# P26_EXPORT.net
KiCad netlist of a schematic drawn in Altium Designer
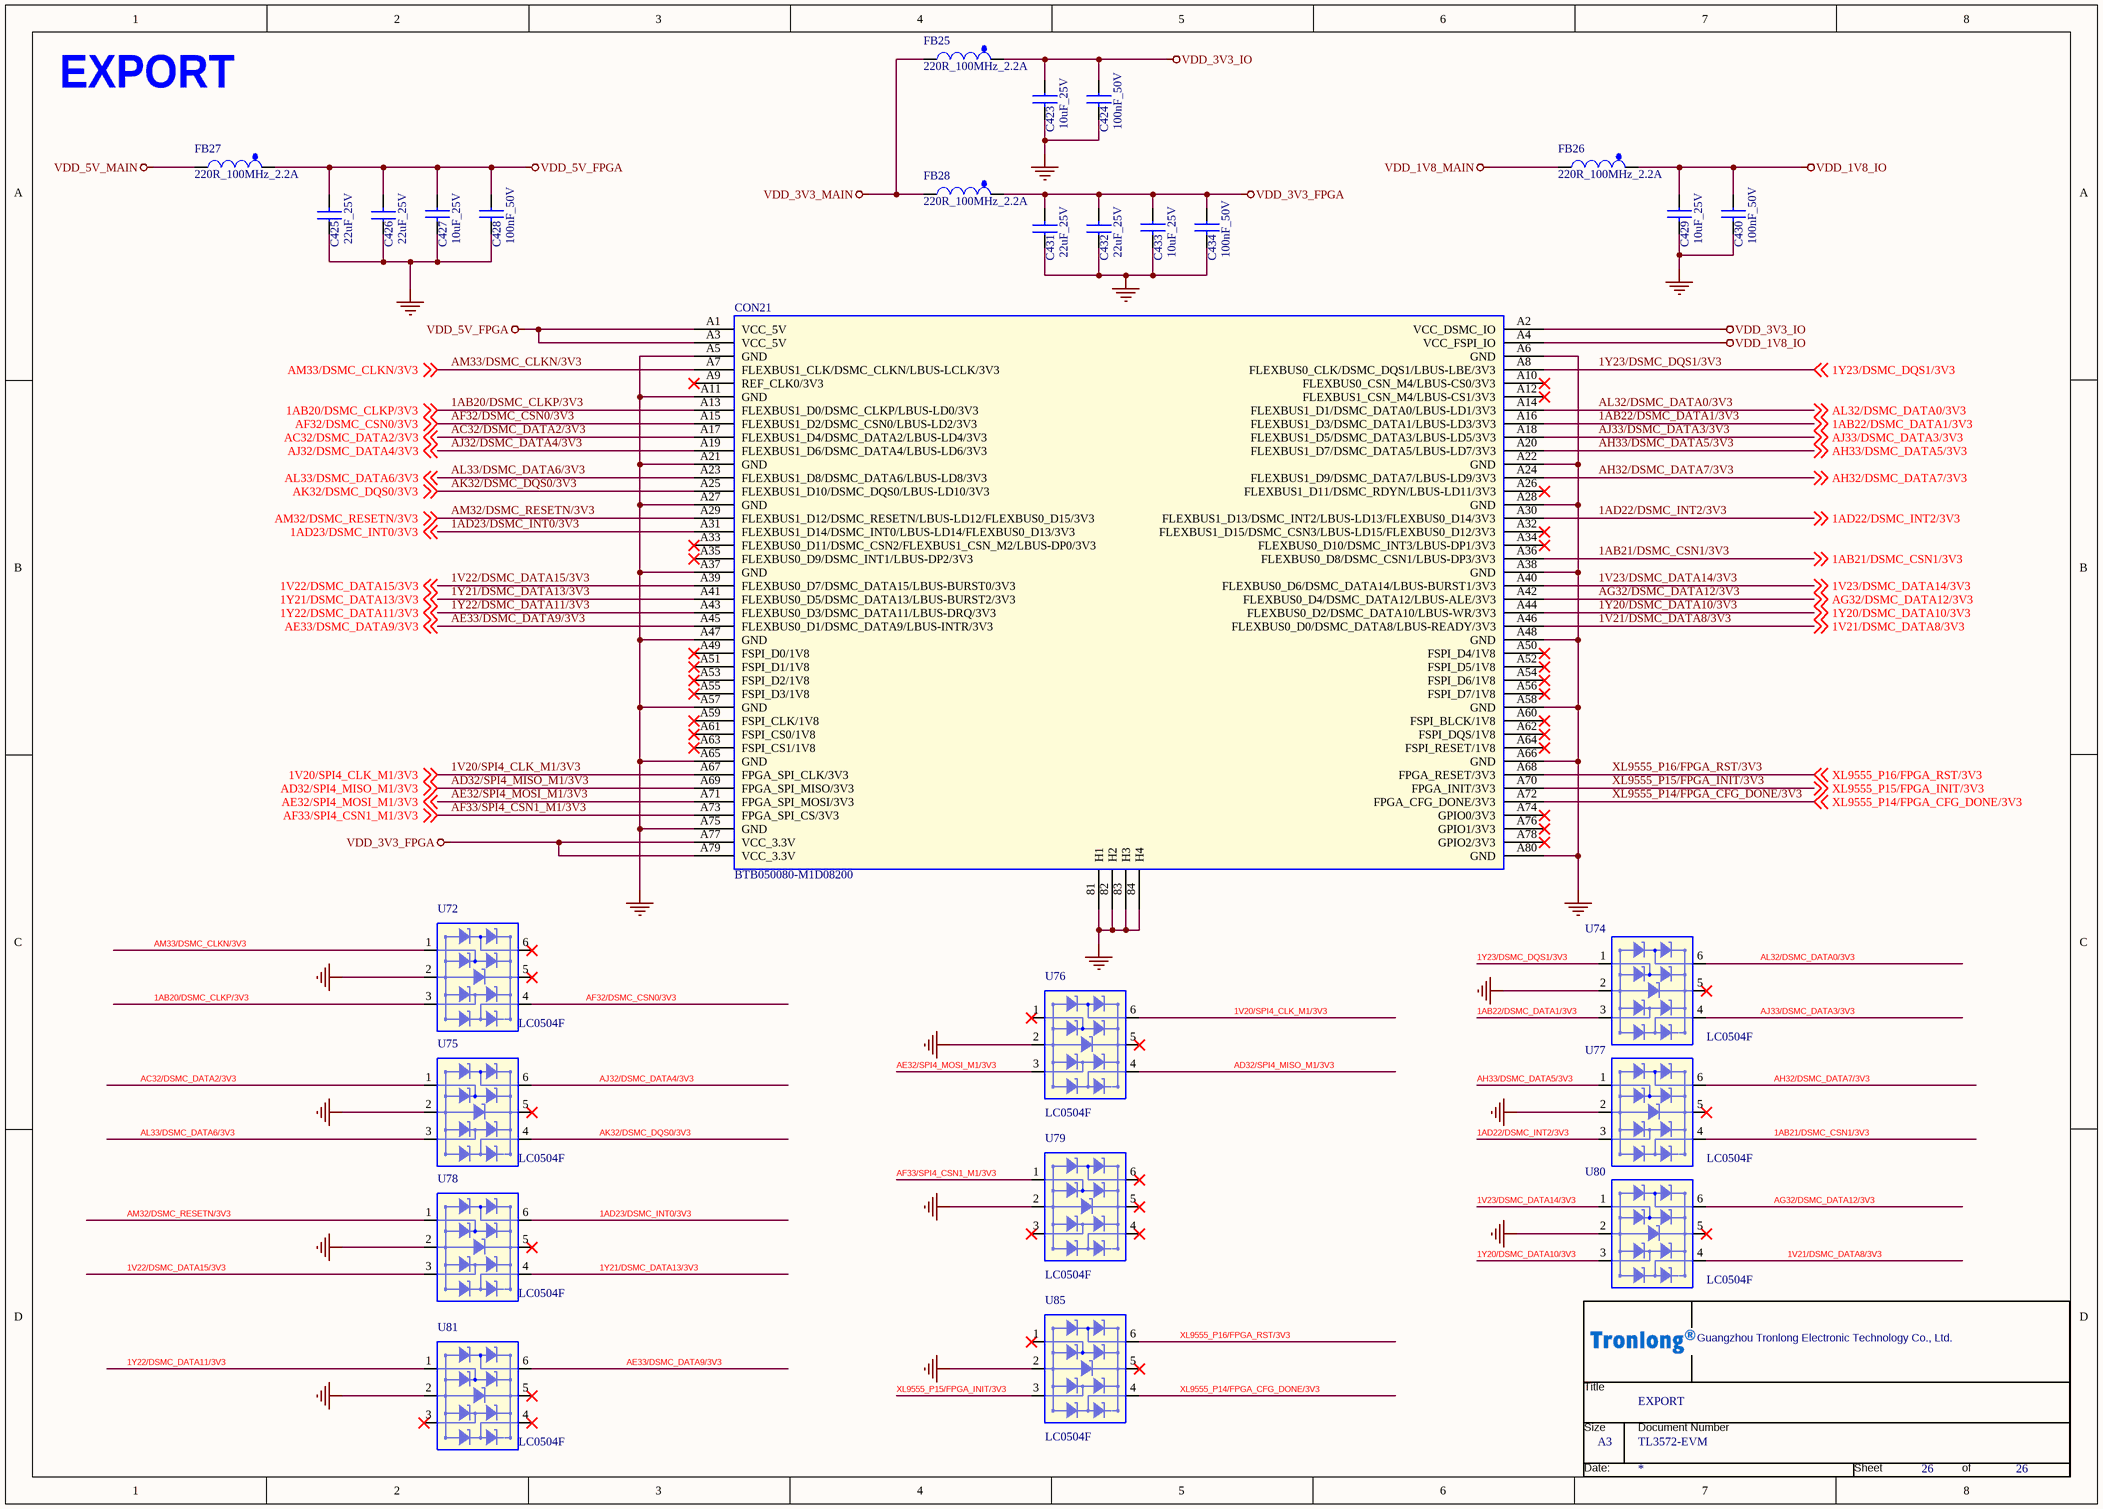
[diagram p0: P26_EXPORT.SchDoc]

(export (version "E")
  (design (tool "Eeschema 10.0.6"))
  (components
    (comp (ref "*")
      (value "TL_NEW")
      (fields
        (field (name "PAGE COUNT") "26")
        (field (name "PAGE NUMBER") "26")
        (field (name "PAGE SIZE") "A3")
        (field (name "ORGNAME") "Guangzhou Tronlong Electronic Technology Co., Ltd.")
        (field (name "TITLE") "EXPORT")
        (field (name "DOC") "TL3572-EVM")
      )
      (libsource (lib "*") (part "TL_NEW"))
    )
    (comp (ref "C423")
      (value "10uF_25V")
      (footprint "C0603")
      (description "贴片陶瓷电容,10uF,20%,25V,X5R")
      (fields
        (field (name "MANUFACTURER PARTNUMBER") "0603X106M250NT")
        (field (name "MANUFACTURER") "广东风华高新科技股份有限公司（FH）")
      )
      (libsource (lib "*") (part "CAP NP_Dup2"))
    )
    (comp (ref "C424")
      (value "100nF_50V")
      (footprint "C0402")
      (description "贴片陶瓷电容,100nF,10%,50V,X7R")
      (fields
        (field (name "MANUFACTURER PARTNUMBER") "0402B104K500NT")
        (field (name "MANUFACTURER") "广东风华高新科技股份有限公司（FH）")
      )
      (libsource (lib "*") (part "CAP NP_Dup2"))
    )
    (comp (ref "C425")
      (value "22uF_25V")
      (footprint "C0805")
      (description "贴片陶瓷电容,22uF,20%,25V,X5R")
      (fields
        (field (name "MANUFACTURER") "广东风华高新科技股份有限公司（FH）")
        (field (name "MANUFACTURER PARTNUMBER") "0805X226M250NT")
      )
      (libsource (lib "*") (part "CAP NP_Dup1"))
    )
    (comp (ref "C426")
      (value "22uF_25V")
      (footprint "C0805")
      (description "贴片陶瓷电容,22uF,20%,25V,X5R")
      (fields
        (field (name "MANUFACTURER") "广东风华高新科技股份有限公司（FH）")
        (field (name "MANUFACTURER PARTNUMBER") "0805X226M250NT")
      )
      (libsource (lib "*") (part "CAP NP_Dup1"))
    )
    (comp (ref "C427")
      (value "10uF_25V")
      (footprint "C0603")
      (description "贴片陶瓷电容,10uF,20%,25V,X5R")
      (fields
        (field (name "MANUFACTURER") "广东风华高新科技股份有限公司（FH）")
        (field (name "MANUFACTURER PARTNUMBER") "0603X106M250NT")
      )
      (libsource (lib "*") (part "CAP NP_Dup2"))
    )
    (comp (ref "C428")
      (value "100nF_50V")
      (footprint "C0402")
      (description "贴片陶瓷电容,100nF,10%,50V,X7R")
      (fields
        (field (name "MANUFACTURER") "广东风华高新科技股份有限公司（FH）")
        (field (name "MANUFACTURER PARTNUMBER") "0402B104K500NT")
      )
      (libsource (lib "*") (part "CAP NP_Dup2"))
    )
    (comp (ref "C429")
      (value "10uF_25V")
      (footprint "C0603")
      (description "贴片陶瓷电容,10uF,20%,25V,X5R")
      (fields
        (field (name "MANUFACTURER") "广东风华高新科技股份有限公司（FH）")
        (field (name "MANUFACTURER PARTNUMBER") "0603X106M250NT")
      )
      (libsource (lib "*") (part "CAP NP_Dup2"))
    )
    (comp (ref "C430")
      (value "100nF_50V")
      (footprint "C0402")
      (description "贴片陶瓷电容,100nF,10%,50V,X7R")
      (fields
        (field (name "MANUFACTURER PARTNUMBER") "0402B104K500NT")
        (field (name "MANUFACTURER") "广东风华高新科技股份有限公司（FH）")
      )
      (libsource (lib "*") (part "CAP NP_Dup2"))
    )
    (comp (ref "C431")
      (value "22uF_25V")
      (footprint "C0805")
      (description "贴片陶瓷电容,22uF,20%,25V,X5R")
      (fields
        (field (name "MANUFACTURER") "广东风华高新科技股份有限公司（FH）")
        (field (name "MANUFACTURER PARTNUMBER") "0805X226M250NT")
      )
      (libsource (lib "*") (part "CAP NP_Dup1"))
    )
    (comp (ref "C432")
      (value "22uF_25V")
      (footprint "C0805")
      (description "贴片陶瓷电容,22uF,20%,25V,X5R")
      (fields
        (field (name "MANUFACTURER") "广东风华高新科技股份有限公司（FH）")
        (field (name "MANUFACTURER PARTNUMBER") "0805X226M250NT")
      )
      (libsource (lib "*") (part "CAP NP_Dup1"))
    )
    (comp (ref "C433")
      (value "10uF_25V")
      (footprint "C0603")
      (description "贴片陶瓷电容,10uF,20%,25V,X5R")
      (fields
        (field (name "MANUFACTURER") "广东风华高新科技股份有限公司（FH）")
        (field (name "MANUFACTURER PARTNUMBER") "0603X106M250NT")
      )
      (libsource (lib "*") (part "CAP NP_Dup2"))
    )
    (comp (ref "C434")
      (value "100nF_50V")
      (footprint "C0402")
      (description "贴片陶瓷电容,100nF,10%,50V,X7R")
      (fields
        (field (name "MANUFACTURER") "广东风华高新科技股份有限公司（FH）")
        (field (name "MANUFACTURER PARTNUMBER") "0402B104K500NT")
      )
      (libsource (lib "*") (part "CAP NP_Dup2"))
    )
    (comp (ref "CON21")
      (value "BTB050080-M1D08200")
      (footprint "TL-AD-PGL25G")
      (description "B2B连接器,2x40P,0.5mm间距,公座,高度1.0mm,黑色,贴片")
      (fields (field (name "MANUFACTURER") "深圳市爱特姆科技有限公司（ATOM）"))
      (libsource (lib "*") (part "TL-AD-PGL25G_6"))
    )
    (comp (ref "FB25")
      (value "220R_100MHz_2.2A")
      (footprint "L0603")
      (description "磁珠,50mΩ,2.2A,220R@100MHz")
      (fields
        (field (name "MANUFACTURER PARTNUMBER") "UPZ1608U221-2R2TF")
        (field (name "MANUFACTURER") "深圳顺络电子股份有限公司（Sunlord）")
      )
      (libsource (lib "*") (part "FERRITE BEAD_Dup1"))
    )
    (comp (ref "FB26")
      (value "220R_100MHz_2.2A")
      (footprint "L0603")
      (description "磁珠,50mΩ,2.2A,220R@100MHz")
      (fields
        (field (name "MANUFACTURER") "深圳顺络电子股份有限公司（Sunlord）")
        (field (name "MANUFACTURER PARTNUMBER") "UPZ1608U221-2R2TF")
      )
      (libsource (lib "*") (part "FERRITE BEAD_Dup1"))
    )
    (comp (ref "FB27")
      (value "220R_100MHz_2.2A")
      (footprint "L0603")
      (description "磁珠,50mΩ,2.2A,220R@100MHz")
      (fields
        (field (name "MANUFACTURER") "深圳顺络电子股份有限公司（Sunlord）")
        (field (name "MANUFACTURER PARTNUMBER") "UPZ1608U221-2R2TF")
      )
      (libsource (lib "*") (part "FERRITE BEAD_Dup1"))
    )
    (comp (ref "FB28")
      (value "220R_100MHz_2.2A")
      (footprint "L0603")
      (description "磁珠,50mΩ,2.2A,220R@100MHz")
      (fields
        (field (name "MANUFACTURER PARTNUMBER") "UPZ1608U221-2R2TF")
        (field (name "MANUFACTURER") "深圳顺络电子股份有限公司（Sunlord）")
      )
      (libsource (lib "*") (part "FERRITE BEAD_Dup1"))
    )
    (comp (ref "U72")
      (value "LC0504F")
      (footprint "SOT363")
      (description "ESD二极管,VRWM=5V,VBR=6V,四组,单向,8KV,15KV")
      (fields (field (name "MANUFACTURER") "上海雷卯电子科技有限公司（Leiditech）"))
      (libsource (lib "*") (part "PRTR5V0U4Y"))
    )
    (comp (ref "U74")
      (value "LC0504F")
      (footprint "SOT363")
      (description "ESD二极管,VRWM=5V,VBR=6V,四组,单向,8KV,15KV")
      (fields (field (name "MANUFACTURER") "上海雷卯电子科技有限公司（Leiditech）"))
      (libsource (lib "*") (part "PRTR5V0U4Y"))
    )
    (comp (ref "U75")
      (value "LC0504F")
      (footprint "SOT363")
      (description "ESD二极管,VRWM=5V,VBR=6V,四组,单向,8KV,15KV")
      (fields (field (name "MANUFACTURER") "上海雷卯电子科技有限公司（Leiditech）"))
      (libsource (lib "*") (part "PRTR5V0U4Y"))
    )
    (comp (ref "U76")
      (value "LC0504F")
      (footprint "SOT363")
      (description "ESD二极管,VRWM=5V,VBR=6V,四组,单向,8KV,15KV")
      (fields (field (name "MANUFACTURER") "上海雷卯电子科技有限公司（Leiditech）"))
      (libsource (lib "*") (part "PRTR5V0U4Y"))
    )
    (comp (ref "U77")
      (value "LC0504F")
      (footprint "SOT363")
      (description "ESD二极管,VRWM=5V,VBR=6V,四组,单向,8KV,15KV")
      (fields (field (name "MANUFACTURER") "上海雷卯电子科技有限公司（Leiditech）"))
      (libsource (lib "*") (part "PRTR5V0U4Y"))
    )
    (comp (ref "U78")
      (value "LC0504F")
      (footprint "SOT363")
      (description "ESD二极管,VRWM=5V,VBR=6V,四组,单向,8KV,15KV")
      (fields (field (name "MANUFACTURER") "上海雷卯电子科技有限公司（Leiditech）"))
      (libsource (lib "*") (part "PRTR5V0U4Y"))
    )
    (comp (ref "U79")
      (value "LC0504F")
      (footprint "SOT363")
      (description "ESD二极管,VRWM=5V,VBR=6V,四组,单向,8KV,15KV")
      (fields (field (name "MANUFACTURER") "上海雷卯电子科技有限公司（Leiditech）"))
      (libsource (lib "*") (part "PRTR5V0U4Y"))
    )
    (comp (ref "U80")
      (value "LC0504F")
      (footprint "SOT363")
      (description "ESD二极管,VRWM=5V,VBR=6V,四组,单向,8KV,15KV")
      (fields (field (name "MANUFACTURER") "上海雷卯电子科技有限公司（Leiditech）"))
      (libsource (lib "*") (part "PRTR5V0U4Y"))
    )
    (comp (ref "U81")
      (value "LC0504F")
      (footprint "SOT363")
      (description "ESD二极管,VRWM=5V,VBR=6V,四组,单向,8KV,15KV")
      (fields (field (name "MANUFACTURER") "上海雷卯电子科技有限公司（Leiditech）"))
      (libsource (lib "*") (part "PRTR5V0U4Y"))
    )
    (comp (ref "U85")
      (value "LC0504F")
      (footprint "SOT363")
      (description "ESD二极管,VRWM=5V,VBR=6V,四组,单向,8KV,15KV")
      (fields (field (name "MANUFACTURER") "上海雷卯电子科技有限公司（Leiditech）"))
      (libsource (lib "*") (part "PRTR5V0U4Y"))
    )
  )
  (nets
    (net (code "1") (name "1AB20{slash}DSMC_CLKP{slash}3V3") (class "Default")
      (node (ref "CON21") (pin "A13") (pinfunction "FLEXBUS1_D0/DSMC_CLKP/LBUS-LD0/3V3_A13") (pintype "passive"))
      (node (ref "U72") (pin "3") (pinfunction "3_3") (pintype "passive"))
    )
    (net (code "2") (name "1AB21{slash}DSMC_CSN1{slash}3V3") (class "Default")
      (node (ref "CON21") (pin "A36") (pinfunction "FLEXBUS0_D8/DSMC_CSN1/LBUS-DP3/3V3_A36") (pintype "passive"))
      (node (ref "U77") (pin "4") (pinfunction "4_4") (pintype "passive"))
    )
    (net (code "3") (name "1AB22{slash}DSMC_DATA1{slash}3V3") (class "Default")
      (node (ref "CON21") (pin "A16") (pinfunction "FLEXBUS1_D3/DSMC_DATA1/LBUS-LD3/3V3_A16") (pintype "passive"))
      (node (ref "U74") (pin "3") (pinfunction "3_3") (pintype "passive"))
    )
    (net (code "4") (name "1AD22{slash}DSMC_INT2{slash}3V3") (class "Default")
      (node (ref "CON21") (pin "A30") (pinfunction "FLEXBUS1_D13/DSMC_INT2/LBUS-LD13/FLEXBUS0_D14/3V3_A30") (pintype "passive"))
      (node (ref "U77") (pin "3") (pinfunction "3_3") (pintype "passive"))
    )
    (net (code "5") (name "1AD23{slash}DSMC_INT0{slash}3V3") (class "Default")
      (node (ref "CON21") (pin "A31") (pinfunction "FLEXBUS1_D14/DSMC_INT0/LBUS-LD14/FLEXBUS0_D13/3V3_A31") (pintype "passive"))
      (node (ref "U78") (pin "6") (pinfunction "6_6") (pintype "passive"))
    )
    (net (code "6") (name "1V20{slash}SPI4_CLK_M1{slash}3V3") (class "Default")
      (node (ref "CON21") (pin "A67") (pinfunction "FPGA_SPI_CLK/3V3_A67") (pintype "passive"))
      (node (ref "U76") (pin "6") (pinfunction "6_6") (pintype "passive"))
    )
    (net (code "7") (name "1V21{slash}DSMC_DATA8{slash}3V3") (class "Default")
      (node (ref "CON21") (pin "A46") (pinfunction "FLEXBUS0_D0/DSMC_DATA8/LBUS-READY/3V3_A46") (pintype "passive"))
      (node (ref "U80") (pin "4") (pinfunction "4_4") (pintype "passive"))
    )
    (net (code "8") (name "1V22{slash}DSMC_DATA15{slash}3V3") (class "Default")
      (node (ref "CON21") (pin "A39") (pinfunction "FLEXBUS0_D7/DSMC_DATA15/LBUS-BURST0/3V3_A39") (pintype "passive"))
      (node (ref "U78") (pin "3") (pinfunction "3_3") (pintype "passive"))
    )
    (net (code "9") (name "1V23{slash}DSMC_DATA14{slash}3V3") (class "Default")
      (node (ref "CON21") (pin "A40") (pinfunction "FLEXBUS0_D6/DSMC_DATA14/LBUS-BURST1/3V3_A40") (pintype "passive"))
      (node (ref "U80") (pin "1") (pinfunction "1_1") (pintype "passive"))
    )
    (net (code "10") (name "1Y20{slash}DSMC_DATA10{slash}3V3") (class "Default")
      (node (ref "CON21") (pin "A44") (pinfunction "FLEXBUS0_D2/DSMC_DATA10/LBUS-WR/3V3_A44") (pintype "passive"))
      (node (ref "U80") (pin "3") (pinfunction "3_3") (pintype "passive"))
    )
    (net (code "11") (name "1Y21{slash}DSMC_DATA13{slash}3V3") (class "Default")
      (node (ref "CON21") (pin "A41") (pinfunction "FLEXBUS0_D5/DSMC_DATA13/LBUS-BURST2/3V3_A41") (pintype "passive"))
      (node (ref "U78") (pin "4") (pinfunction "4_4") (pintype "passive"))
    )
    (net (code "12") (name "1Y22{slash}DSMC_DATA11{slash}3V3") (class "Default")
      (node (ref "CON21") (pin "A43") (pinfunction "FLEXBUS0_D3/DSMC_DATA11/LBUS-DRQ/3V3_A43") (pintype "passive"))
      (node (ref "U81") (pin "1") (pinfunction "1_1") (pintype "passive"))
    )
    (net (code "13") (name "1Y23{slash}DSMC_DQS1{slash}3V3") (class "Default")
      (node (ref "CON21") (pin "A8") (pinfunction "FLEXBUS0_CLK/DSMC_DQS1/LBUS-LBE/3V3_A8") (pintype "passive"))
      (node (ref "U74") (pin "1") (pinfunction "1_1") (pintype "passive"))
    )
    (net (code "14") (name "AC32{slash}DSMC_DATA2{slash}3V3") (class "Default")
      (node (ref "CON21") (pin "A17") (pinfunction "FLEXBUS1_D4/DSMC_DATA2/LBUS-LD4/3V3_A17") (pintype "passive"))
      (node (ref "U75") (pin "1") (pinfunction "1_1") (pintype "passive"))
    )
    (net (code "15") (name "AD32{slash}SPI4_MISO_M1{slash}3V3") (class "Default")
      (node (ref "CON21") (pin "A69") (pinfunction "FPGA_SPI_MISO/3V3_A69") (pintype "passive"))
      (node (ref "U76") (pin "4") (pinfunction "4_4") (pintype "passive"))
    )
    (net (code "16") (name "AE32{slash}SPI4_MOSI_M1{slash}3V3") (class "Default")
      (node (ref "CON21") (pin "A71") (pinfunction "FPGA_SPI_MOSI/3V3_A71") (pintype "passive"))
      (node (ref "U76") (pin "3") (pinfunction "3_3") (pintype "passive"))
    )
    (net (code "17") (name "AE33{slash}DSMC_DATA9{slash}3V3") (class "Default")
      (node (ref "CON21") (pin "A45") (pinfunction "FLEXBUS0_D1/DSMC_DATA9/LBUS-INTR/3V3_A45") (pintype "passive"))
      (node (ref "U81") (pin "6") (pinfunction "6_6") (pintype "passive"))
    )
    (net (code "18") (name "AF32{slash}DSMC_CSN0{slash}3V3") (class "Default")
      (node (ref "CON21") (pin "A15") (pinfunction "FLEXBUS1_D2/DSMC_CSN0/LBUS-LD2/3V3_A15") (pintype "passive"))
      (node (ref "U72") (pin "4") (pinfunction "4_4") (pintype "passive"))
    )
    (net (code "19") (name "AF33{slash}SPI4_CSN1_M1{slash}3V3") (class "Default")
      (node (ref "CON21") (pin "A73") (pinfunction "FPGA_SPI_CS/3V3_A73") (pintype "power_in"))
      (node (ref "U79") (pin "1") (pinfunction "1_1") (pintype "passive"))
    )
    (net (code "20") (name "AG32{slash}DSMC_DATA12{slash}3V3") (class "Default")
      (node (ref "CON21") (pin "A42") (pinfunction "FLEXBUS0_D4/DSMC_DATA12/LBUS-ALE/3V3_A42") (pintype "passive"))
      (node (ref "U80") (pin "6") (pinfunction "6_6") (pintype "passive"))
    )
    (net (code "21") (name "AH32{slash}DSMC_DATA7{slash}3V3") (class "Default")
      (node (ref "CON21") (pin "A24") (pinfunction "FLEXBUS1_D9/DSMC_DATA7/LBUS-LD9/3V3_A24") (pintype "passive"))
      (node (ref "U77") (pin "6") (pinfunction "6_6") (pintype "passive"))
    )
    (net (code "22") (name "AH33{slash}DSMC_DATA5{slash}3V3") (class "Default")
      (node (ref "CON21") (pin "A20") (pinfunction "FLEXBUS1_D7/DSMC_DATA5/LBUS-LD7/3V3_A20") (pintype "passive"))
      (node (ref "U77") (pin "1") (pinfunction "1_1") (pintype "passive"))
    )
    (net (code "23") (name "AJ32{slash}DSMC_DATA4{slash}3V3") (class "Default")
      (node (ref "CON21") (pin "A19") (pinfunction "FLEXBUS1_D6/DSMC_DATA4/LBUS-LD6/3V3_A19") (pintype "passive"))
      (node (ref "U75") (pin "6") (pinfunction "6_6") (pintype "passive"))
    )
    (net (code "24") (name "AJ33{slash}DSMC_DATA3{slash}3V3") (class "Default")
      (node (ref "CON21") (pin "A18") (pinfunction "FLEXBUS1_D5/DSMC_DATA3/LBUS-LD5/3V3_A18") (pintype "passive"))
      (node (ref "U74") (pin "4") (pinfunction "4_4") (pintype "passive"))
    )
    (net (code "25") (name "AK32{slash}DSMC_DQS0{slash}3V3") (class "Default")
      (node (ref "CON21") (pin "A25") (pinfunction "FLEXBUS1_D10/DSMC_DQS0/LBUS-LD10/3V3_A25") (pintype "passive"))
      (node (ref "U75") (pin "4") (pinfunction "4_4") (pintype "passive"))
    )
    (net (code "26") (name "AL32{slash}DSMC_DATA0{slash}3V3") (class "Default")
      (node (ref "CON21") (pin "A14") (pinfunction "FLEXBUS1_D1/DSMC_DATA0/LBUS-LD1/3V3_A14") (pintype "passive"))
      (node (ref "U74") (pin "6") (pinfunction "6_6") (pintype "passive"))
    )
    (net (code "27") (name "AL33{slash}DSMC_DATA6{slash}3V3") (class "Default")
      (node (ref "CON21") (pin "A23") (pinfunction "FLEXBUS1_D8/DSMC_DATA6/LBUS-LD8/3V3_A23") (pintype "passive"))
      (node (ref "U75") (pin "3") (pinfunction "3_3") (pintype "passive"))
    )
    (net (code "28") (name "AM32{slash}DSMC_RESETN{slash}3V3") (class "Default")
      (node (ref "CON21") (pin "A29") (pinfunction "FLEXBUS1_D12/DSMC_RESETN/LBUS-LD12/FLEXBUS0_D15/3V3_A29") (pintype "passive"))
      (node (ref "U78") (pin "1") (pinfunction "1_1") (pintype "passive"))
    )
    (net (code "29") (name "AM33{slash}DSMC_CLKN{slash}3V3") (class "Default")
      (node (ref "CON21") (pin "A7") (pinfunction "FLEXBUS1_CLK/DSMC_CLKN/LBUS-LCLK/3V3_A7") (pintype "passive"))
      (node (ref "U72") (pin "1") (pinfunction "1_1") (pintype "passive"))
    )
    (net (code "30") (name "GND") (class "Default")
      (node (ref "C423") (pin "2") (pinfunction "2_2") (pintype "passive"))
      (node (ref "C424") (pin "2") (pinfunction "2_2") (pintype "passive"))
      (node (ref "C425") (pin "1") (pinfunction "1_1") (pintype "passive"))
      (node (ref "C426") (pin "1") (pinfunction "1_1") (pintype "passive"))
      (node (ref "C427") (pin "2") (pinfunction "2_2") (pintype "passive"))
      (node (ref "C428") (pin "2") (pinfunction "2_2") (pintype "passive"))
      (node (ref "C429") (pin "2") (pinfunction "2_2") (pintype "passive"))
      (node (ref "C430") (pin "2") (pinfunction "2_2") (pintype "passive"))
      (node (ref "C431") (pin "1") (pinfunction "1_1") (pintype "passive"))
      (node (ref "C432") (pin "1") (pinfunction "1_1") (pintype "passive"))
      (node (ref "C433") (pin "2") (pinfunction "2_2") (pintype "passive"))
      (node (ref "C434") (pin "2") (pinfunction "2_2") (pintype "passive"))
      (node (ref "CON21") (pin "81") (pinfunction "H1_81") (pintype "passive"))
      (node (ref "CON21") (pin "82") (pinfunction "H2_82") (pintype "passive"))
      (node (ref "CON21") (pin "83") (pinfunction "H3_83") (pintype "passive"))
      (node (ref "CON21") (pin "84") (pinfunction "H4_84") (pintype "passive"))
      (node (ref "CON21") (pin "A11") (pinfunction "GND_A11") (pintype "power_in"))
      (node (ref "CON21") (pin "A21") (pinfunction "GND_A21") (pintype "power_in"))
      (node (ref "CON21") (pin "A22") (pinfunction "GND_A22") (pintype "power_in"))
      (node (ref "CON21") (pin "A27") (pinfunction "GND_A27") (pintype "power_in"))
      (node (ref "CON21") (pin "A28") (pinfunction "GND_A28") (pintype "power_in"))
      (node (ref "CON21") (pin "A37") (pinfunction "GND_A37") (pintype "power_in"))
      (node (ref "CON21") (pin "A38") (pinfunction "GND_A38") (pintype "power_in"))
      (node (ref "CON21") (pin "A47") (pinfunction "GND_A47") (pintype "power_in"))
      (node (ref "CON21") (pin "A48") (pinfunction "GND_A48") (pintype "power_in"))
      (node (ref "CON21") (pin "A5") (pinfunction "GND_A5") (pintype "power_in"))
      (node (ref "CON21") (pin "A57") (pinfunction "GND_A57") (pintype "power_in"))
      (node (ref "CON21") (pin "A58") (pinfunction "GND_A58") (pintype "power_in"))
      (node (ref "CON21") (pin "A6") (pinfunction "GND_A6") (pintype "power_in"))
      (node (ref "CON21") (pin "A65") (pinfunction "GND_A65") (pintype "power_in"))
      (node (ref "CON21") (pin "A66") (pinfunction "GND_A66") (pintype "power_in"))
      (node (ref "CON21") (pin "A75") (pinfunction "GND_A75") (pintype "power_in"))
      (node (ref "CON21") (pin "A80") (pinfunction "GND_A80") (pintype "power_in"))
      (node (ref "U72") (pin "2") (pinfunction "2_2") (pintype "passive"))
      (node (ref "U74") (pin "2") (pinfunction "2_2") (pintype "passive"))
      (node (ref "U75") (pin "2") (pinfunction "2_2") (pintype "passive"))
      (node (ref "U76") (pin "2") (pinfunction "2_2") (pintype "passive"))
      (node (ref "U77") (pin "2") (pinfunction "2_2") (pintype "passive"))
      (node (ref "U78") (pin "2") (pinfunction "2_2") (pintype "passive"))
      (node (ref "U79") (pin "2") (pinfunction "2_2") (pintype "passive"))
      (node (ref "U80") (pin "2") (pinfunction "2_2") (pintype "passive"))
      (node (ref "U81") (pin "2") (pinfunction "2_2") (pintype "passive"))
      (node (ref "U85") (pin "2") (pinfunction "2_2") (pintype "passive"))
    )
    (net (code "31") (name "VDD_1V8_IO") (class "Default")
      (node (ref "C429") (pin "1") (pinfunction "1_1") (pintype "passive"))
      (node (ref "C430") (pin "1") (pinfunction "1_1") (pintype "passive"))
      (node (ref "CON21") (pin "A4") (pinfunction "VCC_FSPI_IO_A4") (pintype "power_in"))
      (node (ref "FB26") (pin "1") (pinfunction "1_1") (pintype "passive"))
    )
    (net (code "32") (name "VDD_1V8_MAIN") (class "Default")
      (node (ref "FB26") (pin "2") (pinfunction "2_2") (pintype "passive"))
    )
    (net (code "33") (name "VDD_3V3_FPGA") (class "Default")
      (node (ref "C431") (pin "2") (pinfunction "2_2") (pintype "passive"))
      (node (ref "C432") (pin "2") (pinfunction "2_2") (pintype "passive"))
      (node (ref "C433") (pin "1") (pinfunction "1_1") (pintype "passive"))
      (node (ref "C434") (pin "1") (pinfunction "1_1") (pintype "passive"))
      (node (ref "CON21") (pin "A77") (pinfunction "VCC_3.3V_A77") (pintype "power_in"))
      (node (ref "CON21") (pin "A79") (pinfunction "VCC_3.3V_A79") (pintype "power_in"))
      (node (ref "FB28") (pin "1") (pinfunction "1_1") (pintype "passive"))
    )
    (net (code "34") (name "VDD_3V3_IO") (class "Default")
      (node (ref "C423") (pin "1") (pinfunction "1_1") (pintype "passive"))
      (node (ref "C424") (pin "1") (pinfunction "1_1") (pintype "passive"))
      (node (ref "CON21") (pin "A2") (pinfunction "VCC_DSMC_IO_A2") (pintype "power_in"))
      (node (ref "FB25") (pin "1") (pinfunction "1_1") (pintype "passive"))
    )
    (net (code "35") (name "VDD_3V3_MAIN") (class "Default")
      (node (ref "FB25") (pin "2") (pinfunction "2_2") (pintype "passive"))
      (node (ref "FB28") (pin "2") (pinfunction "2_2") (pintype "passive"))
    )
    (net (code "36") (name "VDD_5V_FPGA") (class "Default")
      (node (ref "C425") (pin "2") (pinfunction "2_2") (pintype "passive"))
      (node (ref "C426") (pin "2") (pinfunction "2_2") (pintype "passive"))
      (node (ref "C427") (pin "1") (pinfunction "1_1") (pintype "passive"))
      (node (ref "C428") (pin "1") (pinfunction "1_1") (pintype "passive"))
      (node (ref "CON21") (pin "A1") (pinfunction "VCC_5V_A1") (pintype "power_in"))
      (node (ref "CON21") (pin "A3") (pinfunction "VCC_5V_A3") (pintype "power_in"))
      (node (ref "FB27") (pin "1") (pinfunction "1_1") (pintype "passive"))
    )
    (net (code "37") (name "VDD_5V_MAIN") (class "Default")
      (node (ref "FB27") (pin "2") (pinfunction "2_2") (pintype "passive"))
    )
    (net (code "38") (name "XL9555_P14{slash}FPGA_CFG_DONE{slash}3V3") (class "Default")
      (node (ref "CON21") (pin "A72") (pinfunction "FPGA_CFG_DONE/3V3_A72") (pintype "passive"))
      (node (ref "U85") (pin "4") (pinfunction "4_4") (pintype "passive"))
    )
    (net (code "39") (name "XL9555_P15{slash}FPGA_INIT{slash}3V3") (class "Default")
      (node (ref "CON21") (pin "A70") (pinfunction "FPGA_INIT/3V3_A70") (pintype "passive"))
      (node (ref "U85") (pin "3") (pinfunction "3_3") (pintype "passive"))
    )
    (net (code "40") (name "XL9555_P16{slash}FPGA_RST{slash}3V3") (class "Default")
      (node (ref "CON21") (pin "A68") (pinfunction "FPGA_RESET/3V3_A68") (pintype "passive"))
      (node (ref "U85") (pin "6") (pinfunction "6_6") (pintype "passive"))
    )
    (net (code "41") (name "unconnected-(CON21-FLEXBUS0_CSN_M4{slash}LBUS-CS0{slash}3V3-PadA10)") (class "Default")
      (node (ref "CON21") (pin "A10") (pinfunction "FLEXBUS0_CSN_M4/LBUS-CS0/3V3_A10") (pintype "passive+no_connect"))
    )
    (net (code "42") (name "unconnected-(CON21-FLEXBUS0_D9{slash}DSMC_INT1{slash}LBUS-DP2{slash}3V3-PadA35)") (class "Default")
      (node (ref "CON21") (pin "A35") (pinfunction "FLEXBUS0_D9/DSMC_INT1/LBUS-DP2/3V3_A35") (pintype "passive+no_connect"))
    )
    (net (code "43") (name "unconnected-(CON21-FLEXBUS0_D10{slash}DSMC_INT3{slash}LBUS-DP1{slash}3V3-PadA34)") (class "Default")
      (node (ref "CON21") (pin "A34") (pinfunction "FLEXBUS0_D10/DSMC_INT3/LBUS-DP1/3V3_A34") (pintype "passive+no_connect"))
    )
    (net (code "44") (name "unconnected-(CON21-FLEXBUS0_D11{slash}DSMC_CSN2{slash}FLEXBUS1_CSN_M2{slash}LBUS-DP0{slash}3V3-PadA33)") (class "Default")
      (node (ref "CON21") (pin "A33") (pinfunction "FLEXBUS0_D11/DSMC_CSN2/FLEXBUS1_CSN_M2/LBUS-DP0/3V3_A33") (pintype "passive+no_connect"))
    )
    (net (code "45") (name "unconnected-(CON21-FLEXBUS1_CSN_M4{slash}LBUS-CS1{slash}3V3-PadA12)") (class "Default")
      (node (ref "CON21") (pin "A12") (pinfunction "FLEXBUS1_CSN_M4/LBUS-CS1/3V3_A12") (pintype "passive+no_connect"))
    )
    (net (code "46") (name "unconnected-(CON21-FLEXBUS1_D11{slash}DSMC_RDYN{slash}LBUS-LD11{slash}3V3-PadA26)") (class "Default")
      (node (ref "CON21") (pin "A26") (pinfunction "FLEXBUS1_D11/DSMC_RDYN/LBUS-LD11/3V3_A26") (pintype "passive+no_connect"))
    )
    (net (code "47") (name "unconnected-(CON21-FLEXBUS1_D15{slash}DSMC_CSN3{slash}LBUS-LD15{slash}FLEXBUS0_D12{slash}3V3-PadA32)") (class "Default")
      (node (ref "CON21") (pin "A32") (pinfunction "FLEXBUS1_D15/DSMC_CSN3/LBUS-LD15/FLEXBUS0_D12/3V3_A32") (pintype "passive+no_connect"))
    )
    (net (code "48") (name "unconnected-(CON21-FSPI_BLCK{slash}1V8-PadA60)") (class "Default")
      (node (ref "CON21") (pin "A60") (pinfunction "FSPI_BLCK/1V8_A60") (pintype "passive+no_connect"))
    )
    (net (code "49") (name "unconnected-(CON21-FSPI_CLK{slash}1V8-PadA59)") (class "Default")
      (node (ref "CON21") (pin "A59") (pinfunction "FSPI_CLK/1V8_A59") (pintype "passive+no_connect"))
    )
    (net (code "50") (name "unconnected-(CON21-FSPI_CS0{slash}1V8-PadA61)") (class "Default")
      (node (ref "CON21") (pin "A61") (pinfunction "FSPI_CS0/1V8_A61") (pintype "passive+no_connect"))
    )
    (net (code "51") (name "unconnected-(CON21-FSPI_CS1{slash}1V8-PadA63)") (class "Default")
      (node (ref "CON21") (pin "A63") (pinfunction "FSPI_CS1/1V8_A63") (pintype "passive+no_connect"))
    )
    (net (code "52") (name "unconnected-(CON21-FSPI_D0{slash}1V8-PadA49)") (class "Default")
      (node (ref "CON21") (pin "A49") (pinfunction "FSPI_D0/1V8_A49") (pintype "passive+no_connect"))
    )
    (net (code "53") (name "unconnected-(CON21-FSPI_D1{slash}1V8-PadA51)") (class "Default")
      (node (ref "CON21") (pin "A51") (pinfunction "FSPI_D1/1V8_A51") (pintype "passive+no_connect"))
    )
    (net (code "54") (name "unconnected-(CON21-FSPI_D2{slash}1V8-PadA53)") (class "Default")
      (node (ref "CON21") (pin "A53") (pinfunction "FSPI_D2/1V8_A53") (pintype "passive+no_connect"))
    )
    (net (code "55") (name "unconnected-(CON21-FSPI_D3{slash}1V8-PadA55)") (class "Default")
      (node (ref "CON21") (pin "A55") (pinfunction "FSPI_D3/1V8_A55") (pintype "passive+no_connect"))
    )
    (net (code "56") (name "unconnected-(CON21-FSPI_D4{slash}1V8-PadA50)") (class "Default")
      (node (ref "CON21") (pin "A50") (pinfunction "FSPI_D4/1V8_A50") (pintype "passive+no_connect"))
    )
    (net (code "57") (name "unconnected-(CON21-FSPI_D5{slash}1V8-PadA52)") (class "Default")
      (node (ref "CON21") (pin "A52") (pinfunction "FSPI_D5/1V8_A52") (pintype "passive+no_connect"))
    )
    (net (code "58") (name "unconnected-(CON21-FSPI_D6{slash}1V8-PadA54)") (class "Default")
      (node (ref "CON21") (pin "A54") (pinfunction "FSPI_D6/1V8_A54") (pintype "passive+no_connect"))
    )
    (net (code "59") (name "unconnected-(CON21-FSPI_D7{slash}1V8-PadA56)") (class "Default")
      (node (ref "CON21") (pin "A56") (pinfunction "FSPI_D7/1V8_A56") (pintype "passive+no_connect"))
    )
    (net (code "60") (name "unconnected-(CON21-FSPI_DQS{slash}1V8-PadA62)") (class "Default")
      (node (ref "CON21") (pin "A62") (pinfunction "FSPI_DQS/1V8_A62") (pintype "passive+no_connect"))
    )
    (net (code "61") (name "unconnected-(CON21-FSPI_RESET{slash}1V8-PadA64)") (class "Default")
      (node (ref "CON21") (pin "A64") (pinfunction "FSPI_RESET/1V8_A64") (pintype "passive+no_connect"))
    )
    (net (code "62") (name "unconnected-(CON21-GPIO0{slash}3V3-PadA74)") (class "Default")
      (node (ref "CON21") (pin "A74") (pinfunction "GPIO0/3V3_A74") (pintype "passive+no_connect"))
    )
    (net (code "63") (name "unconnected-(CON21-GPIO1{slash}3V3-PadA76)") (class "Default")
      (node (ref "CON21") (pin "A76") (pinfunction "GPIO1/3V3_A76") (pintype "passive+no_connect"))
    )
    (net (code "64") (name "unconnected-(CON21-GPIO2{slash}3V3-PadA78)") (class "Default")
      (node (ref "CON21") (pin "A78") (pinfunction "GPIO2/3V3_A78") (pintype "passive+no_connect"))
    )
    (net (code "65") (name "unconnected-(CON21-REF_CLK0{slash}3V3-PadA9)") (class "Default")
      (node (ref "CON21") (pin "A9") (pinfunction "REF_CLK0/3V3_A9") (pintype "passive+no_connect"))
    )
    (net (code "66") (name "unconnected-(U72-Pad5)") (class "Default")
      (node (ref "U72") (pin "5") (pinfunction "5_5") (pintype "passive+no_connect"))
    )
    (net (code "67") (name "unconnected-(U72-Pad6)") (class "Default")
      (node (ref "U72") (pin "6") (pinfunction "6_6") (pintype "passive+no_connect"))
    )
    (net (code "68") (name "unconnected-(U74-Pad5)") (class "Default")
      (node (ref "U74") (pin "5") (pinfunction "5_5") (pintype "passive+no_connect"))
    )
    (net (code "69") (name "unconnected-(U75-Pad5)") (class "Default")
      (node (ref "U75") (pin "5") (pinfunction "5_5") (pintype "passive+no_connect"))
    )
    (net (code "70") (name "unconnected-(U76-Pad1)") (class "Default")
      (node (ref "U76") (pin "1") (pinfunction "1_1") (pintype "passive+no_connect"))
    )
    (net (code "71") (name "unconnected-(U76-Pad5)") (class "Default")
      (node (ref "U76") (pin "5") (pinfunction "5_5") (pintype "passive+no_connect"))
    )
    (net (code "72") (name "unconnected-(U77-Pad5)") (class "Default")
      (node (ref "U77") (pin "5") (pinfunction "5_5") (pintype "passive+no_connect"))
    )
    (net (code "73") (name "unconnected-(U78-Pad5)") (class "Default")
      (node (ref "U78") (pin "5") (pinfunction "5_5") (pintype "passive+no_connect"))
    )
    (net (code "74") (name "unconnected-(U79-Pad3)") (class "Default")
      (node (ref "U79") (pin "3") (pinfunction "3_3") (pintype "passive+no_connect"))
    )
    (net (code "75") (name "unconnected-(U79-Pad4)") (class "Default")
      (node (ref "U79") (pin "4") (pinfunction "4_4") (pintype "passive+no_connect"))
    )
    (net (code "76") (name "unconnected-(U79-Pad5)") (class "Default")
      (node (ref "U79") (pin "5") (pinfunction "5_5") (pintype "passive+no_connect"))
    )
    (net (code "77") (name "unconnected-(U79-Pad6)") (class "Default")
      (node (ref "U79") (pin "6") (pinfunction "6_6") (pintype "passive+no_connect"))
    )
    (net (code "78") (name "unconnected-(U80-Pad5)") (class "Default")
      (node (ref "U80") (pin "5") (pinfunction "5_5") (pintype "passive+no_connect"))
    )
    (net (code "79") (name "unconnected-(U81-Pad3)") (class "Default")
      (node (ref "U81") (pin "3") (pinfunction "3_3") (pintype "passive+no_connect"))
    )
    (net (code "80") (name "unconnected-(U81-Pad4)") (class "Default")
      (node (ref "U81") (pin "4") (pinfunction "4_4") (pintype "passive+no_connect"))
    )
    (net (code "81") (name "unconnected-(U81-Pad5)") (class "Default")
      (node (ref "U81") (pin "5") (pinfunction "5_5") (pintype "passive+no_connect"))
    )
    (net (code "82") (name "unconnected-(U85-Pad1)") (class "Default")
      (node (ref "U85") (pin "1") (pinfunction "1_1") (pintype "passive+no_connect"))
    )
    (net (code "83") (name "unconnected-(U85-Pad5)") (class "Default")
      (node (ref "U85") (pin "5") (pinfunction "5_5") (pintype "passive+no_connect"))
    )
  )
)
